# Apex4ROBOTS_1_0.net
KiCad netlist of a schematic drawn in EAGLE
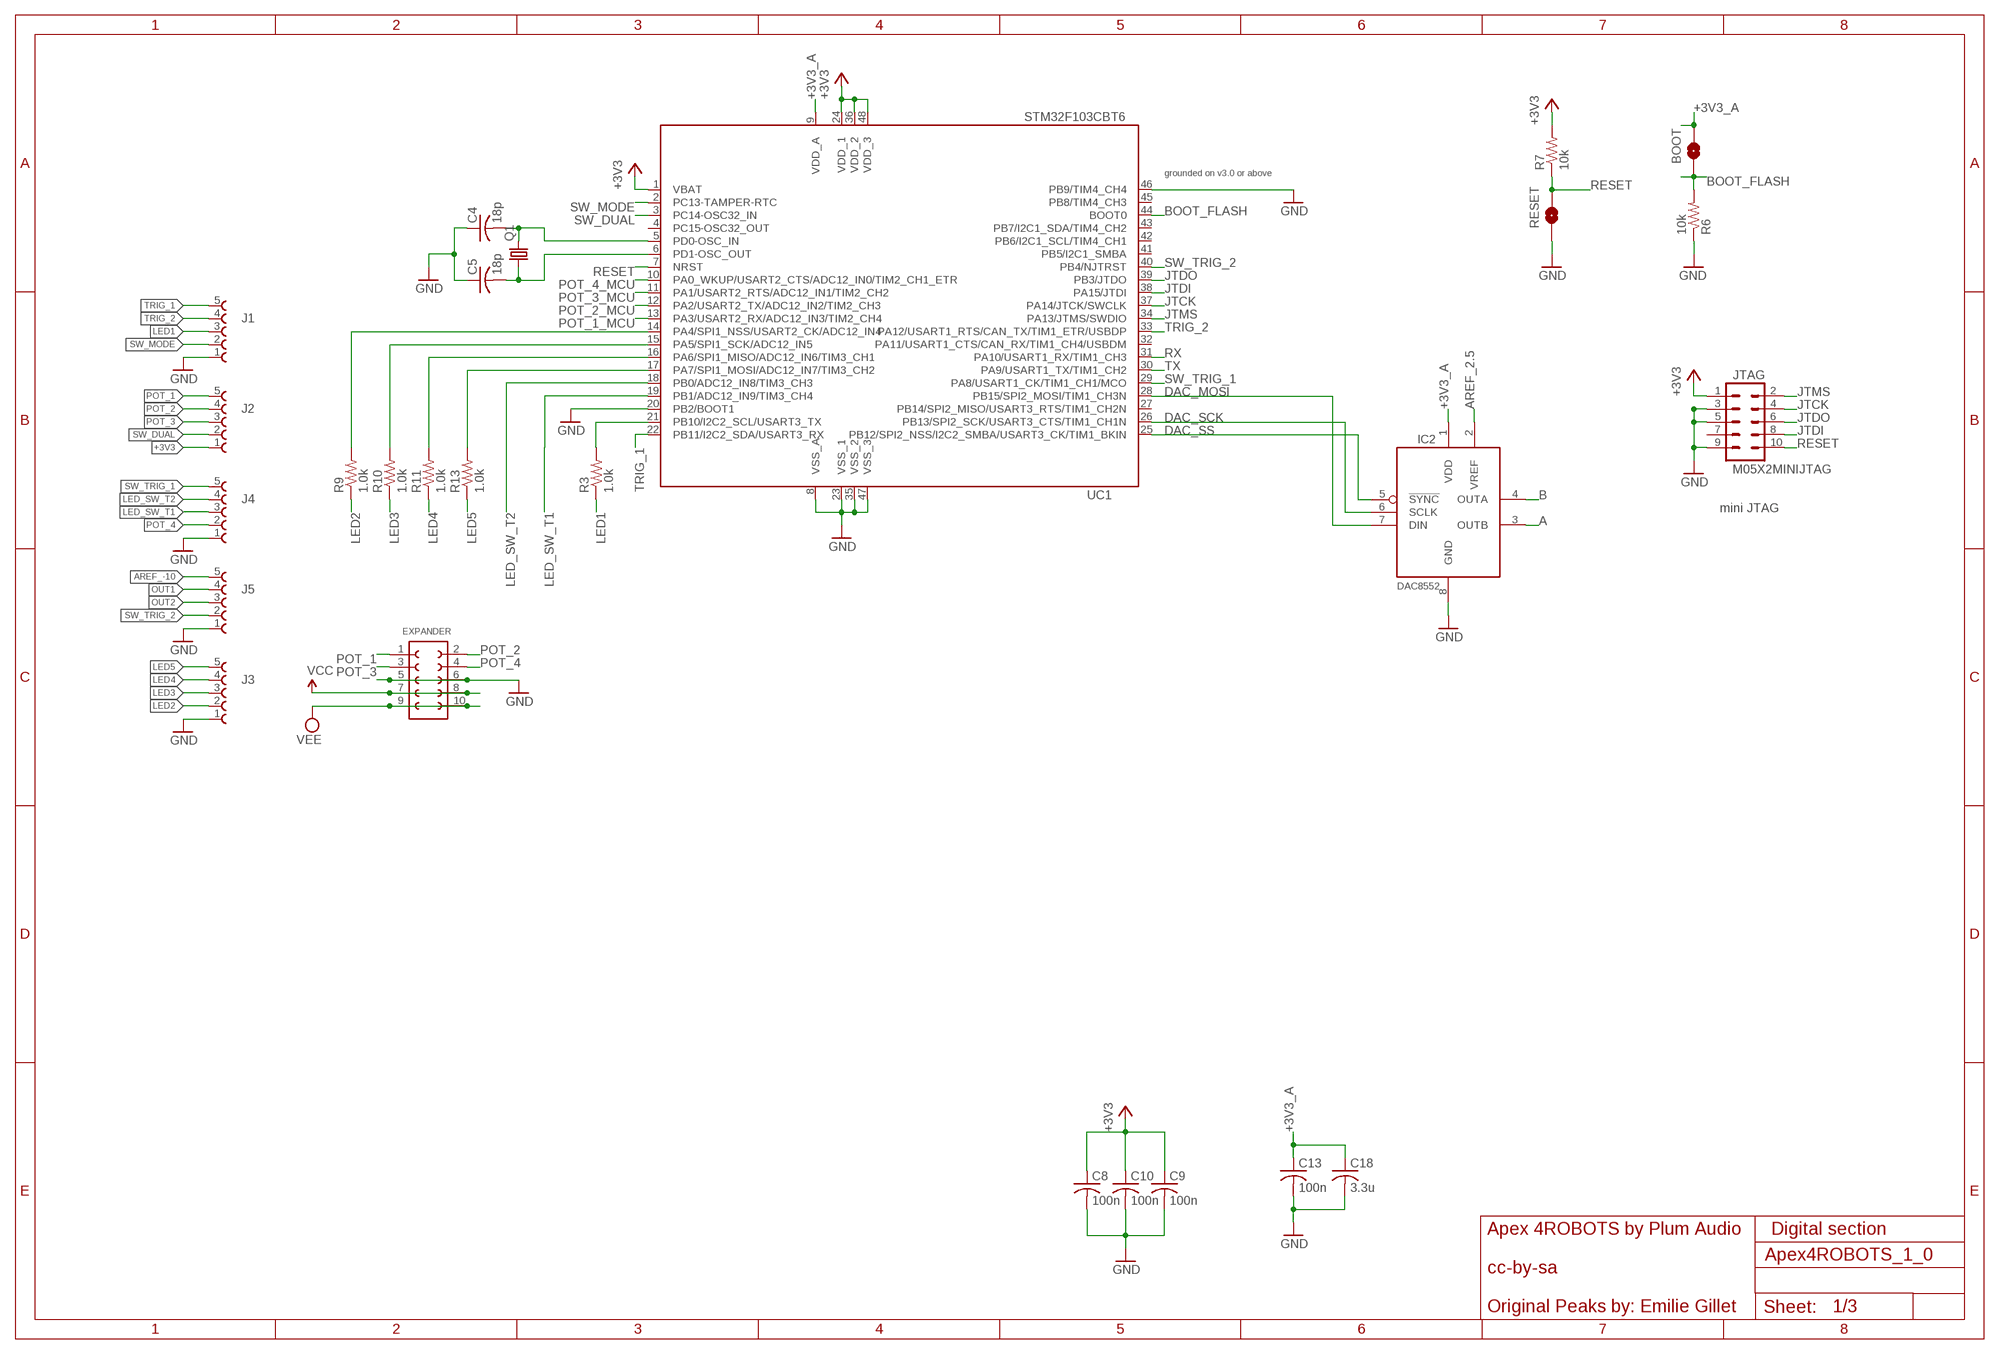
[diagram p0: schematic, sheet 1]
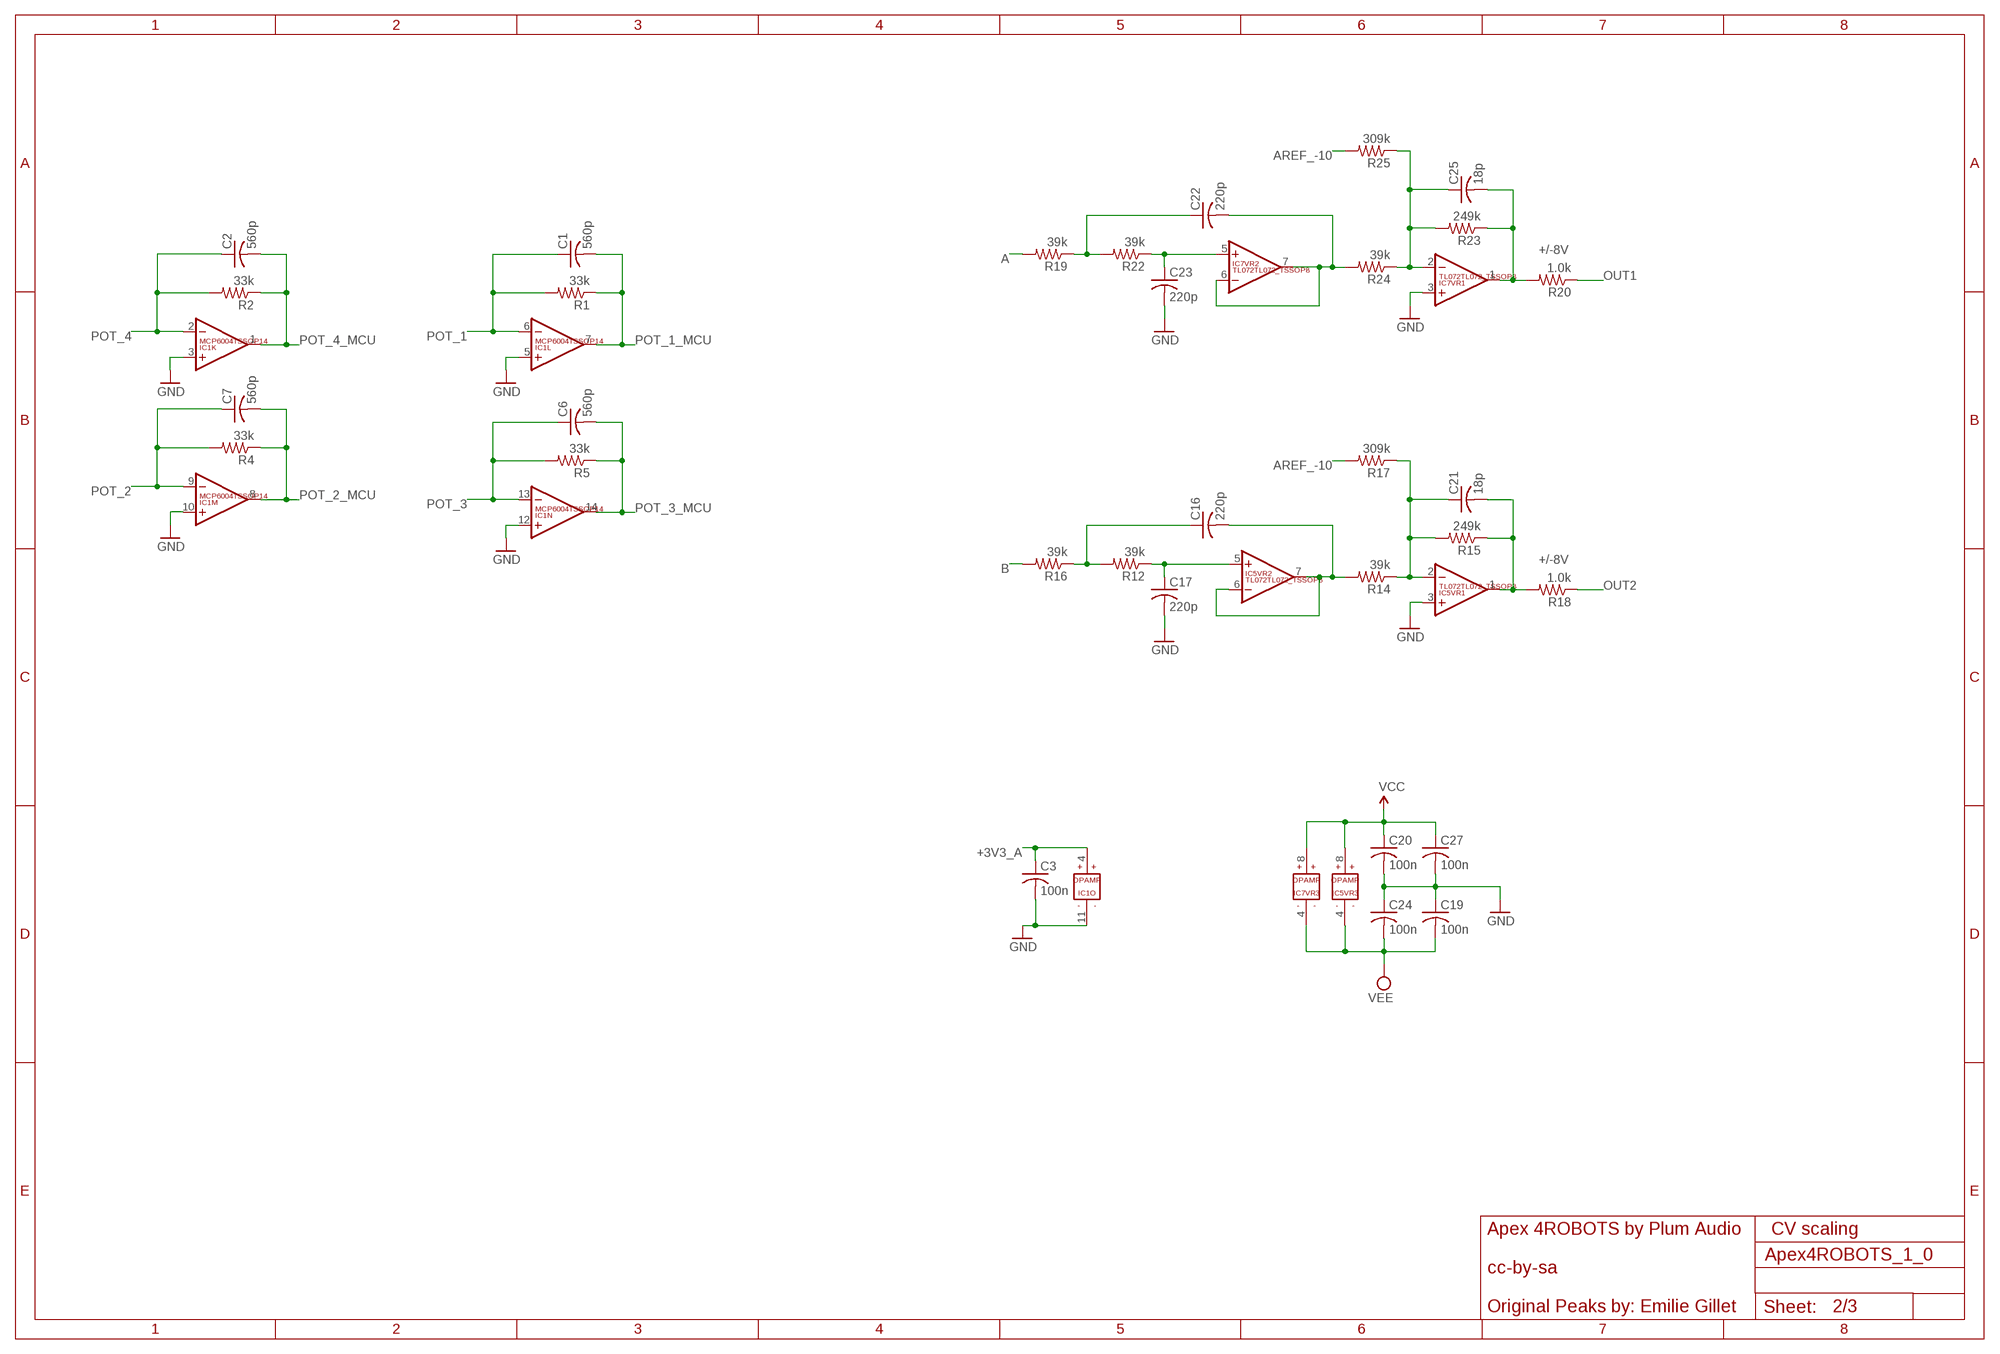
[diagram p1: schematic, sheet 2]
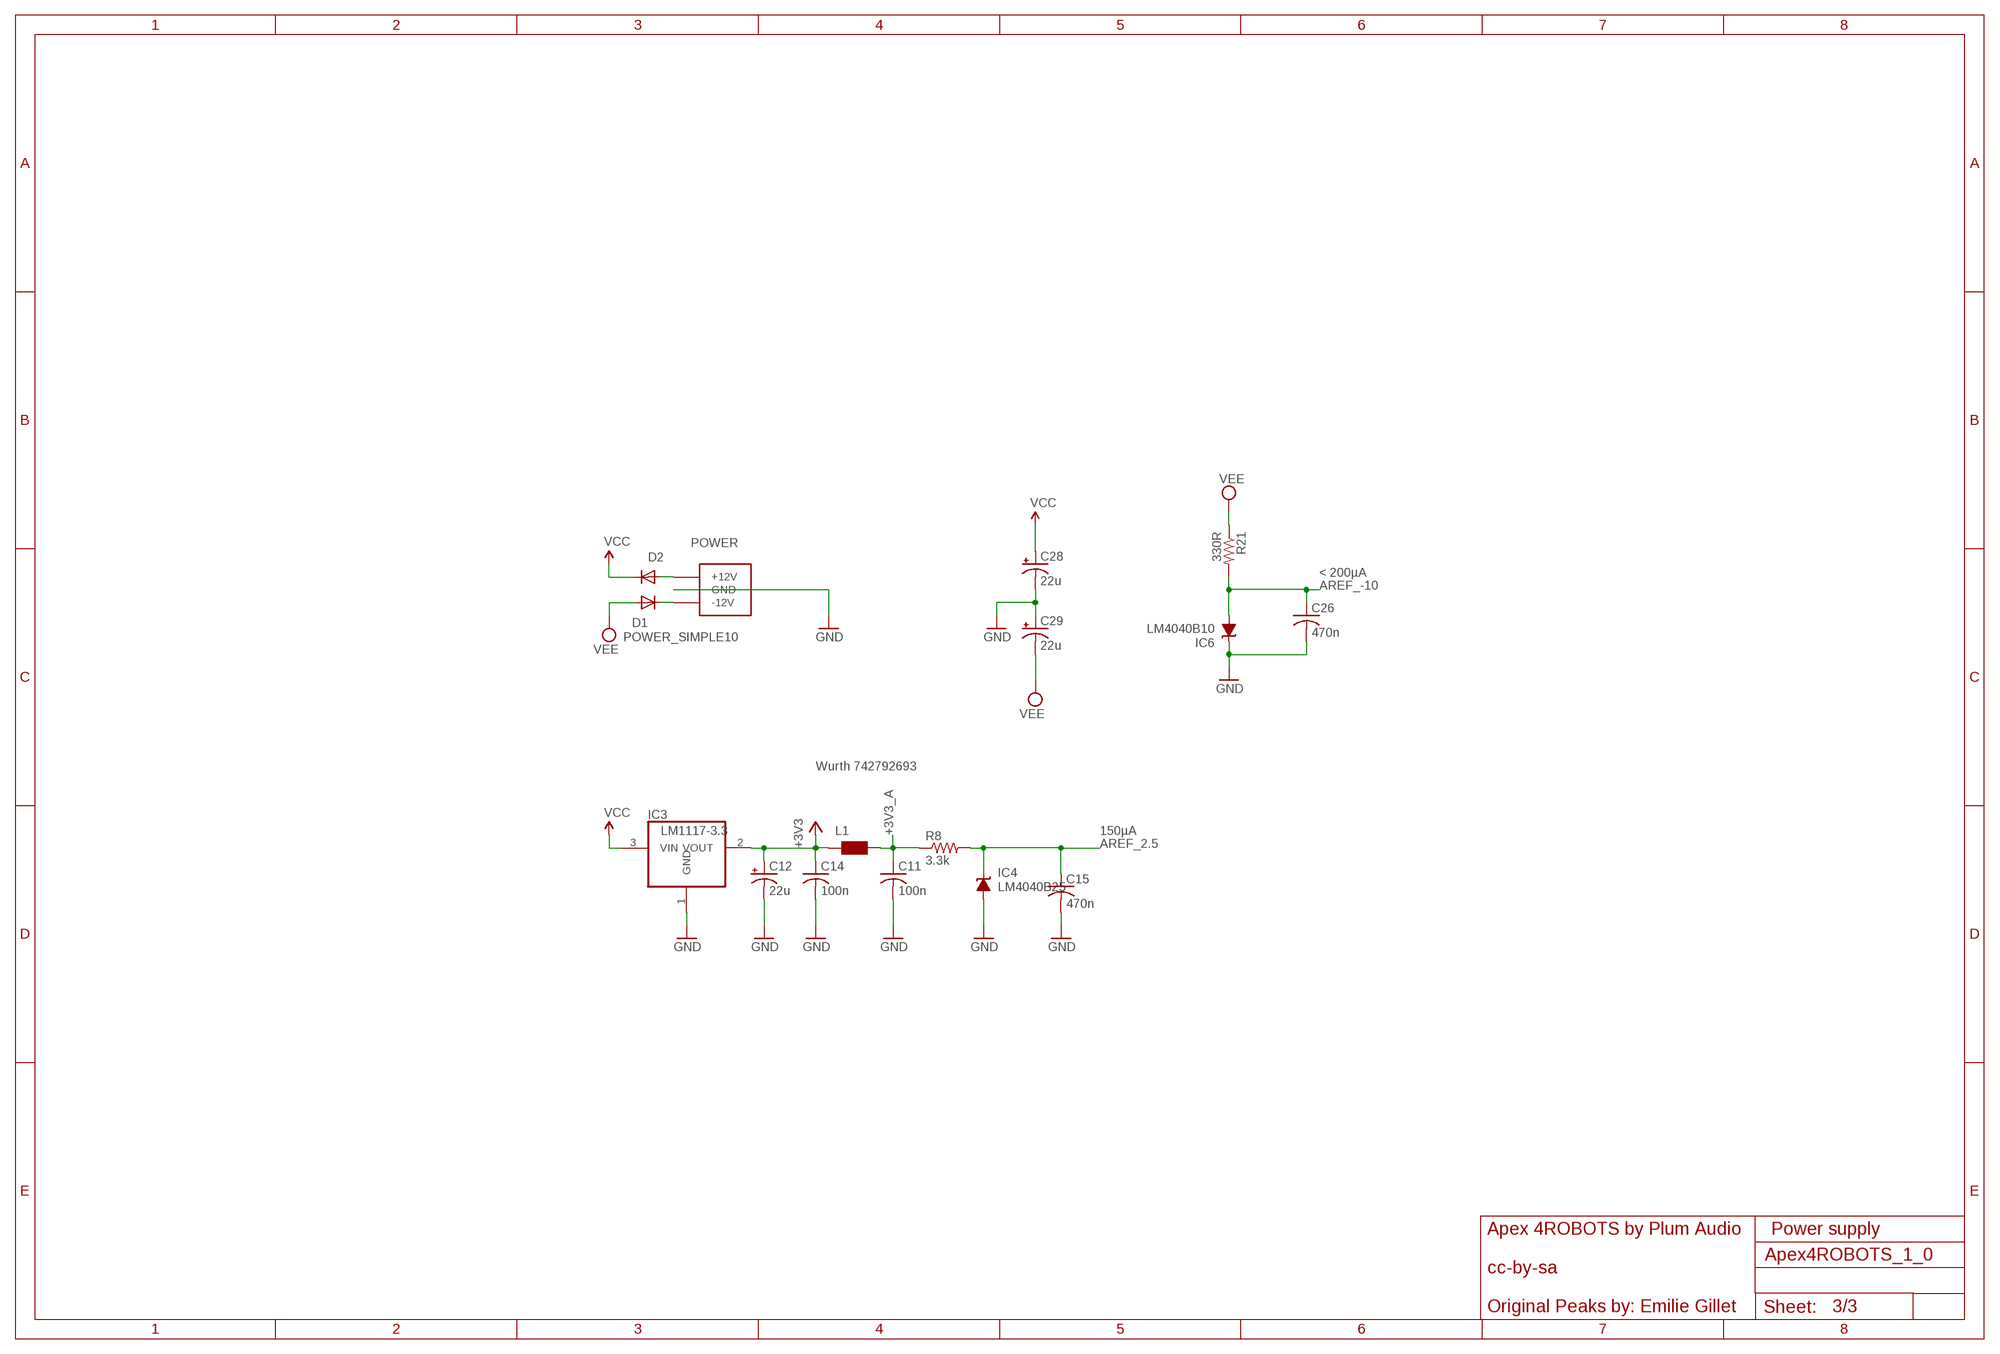
[diagram p2: schematic, sheet 3]

(export (version "E")
  (design (tool "Eeschema 10.0.6"))
  (components
    (comp (ref "C1")
      (value "560p")
      (footprint "eagle-import:C0603")
      (libsource (lib "eagle-import") (part "C-USC0603"))
    )
    (comp (ref "C2")
      (value "560p")
      (footprint "eagle-import:C0603")
      (libsource (lib "eagle-import") (part "C-USC0603"))
    )
    (comp (ref "C3")
      (value "100n")
      (footprint "eagle-import:C0603")
      (libsource (lib "eagle-import") (part "C-USC0603"))
    )
    (comp (ref "C6")
      (value "560p")
      (footprint "eagle-import:C0603")
      (libsource (lib "eagle-import") (part "C-USC0603"))
    )
    (comp (ref "C7")
      (value "560p")
      (footprint "eagle-import:C0603")
      (libsource (lib "eagle-import") (part "C-USC0603"))
    )
    (comp (ref "C16")
      (value "220p")
      (footprint "eagle-import:C0603")
      (libsource (lib "eagle-import") (part "C-USC0603"))
    )
    (comp (ref "C17")
      (value "220p")
      (footprint "eagle-import:C0603")
      (libsource (lib "eagle-import") (part "C-USC0603"))
    )
    (comp (ref "C19")
      (value "100n")
      (footprint "eagle-import:C0603")
      (libsource (lib "eagle-import") (part "C-USC0603"))
    )
    (comp (ref "C20")
      (value "100n")
      (footprint "eagle-import:C0603")
      (libsource (lib "eagle-import") (part "C-USC0603"))
    )
    (comp (ref "C21")
      (value "18p")
      (footprint "eagle-import:C0603")
      (libsource (lib "eagle-import") (part "C-USC0603"))
    )
    (comp (ref "C22")
      (value "220p")
      (footprint "eagle-import:C0603")
      (libsource (lib "eagle-import") (part "C-USC0603"))
    )
    (comp (ref "C23")
      (value "220p")
      (footprint "eagle-import:C0603")
      (libsource (lib "eagle-import") (part "C-USC0603"))
    )
    (comp (ref "C24")
      (value "100n")
      (footprint "eagle-import:C0603")
      (libsource (lib "eagle-import") (part "C-USC0603"))
    )
    (comp (ref "C25")
      (value "18p")
      (footprint "eagle-import:C0603")
      (libsource (lib "eagle-import") (part "C-USC0603"))
    )
    (comp (ref "C27")
      (value "100n")
      (footprint "eagle-import:C0603")
      (libsource (lib "eagle-import") (part "C-USC0603"))
    )
    (comp (ref "IC1")
      (value "MCP6004TSSOP14")
      (footprint "eagle-import:TSSOP14")
      (libsource (lib "eagle-import") (part "MCP6004TSSOP14"))
    )
    (comp (ref "IC5")
      (value "TL072TL072_TSSOP8")
      (footprint "eagle-import:TL072_TSSOP8")
      (libsource (lib "eagle-import") (part "TL072TL072_TSSOP8"))
    )
    (comp (ref "IC7")
      (value "TL072TL072_TSSOP8")
      (footprint "eagle-import:TL072_TSSOP8")
      (libsource (lib "eagle-import") (part "TL072TL072_TSSOP8"))
    )
    (comp (ref "R1")
      (value "33k")
      (footprint "eagle-import:R0603")
      (libsource (lib "eagle-import") (part "R-US_R0603"))
    )
    (comp (ref "R2")
      (value "33k")
      (footprint "eagle-import:R0603")
      (libsource (lib "eagle-import") (part "R-US_R0603"))
    )
    (comp (ref "R4")
      (value "33k")
      (footprint "eagle-import:R0603")
      (libsource (lib "eagle-import") (part "R-US_R0603"))
    )
    (comp (ref "R5")
      (value "33k")
      (footprint "eagle-import:R0603")
      (libsource (lib "eagle-import") (part "R-US_R0603"))
    )
    (comp (ref "R12")
      (value "39k")
      (footprint "eagle-import:R0603")
      (libsource (lib "eagle-import") (part "R-US_R0603"))
    )
    (comp (ref "R14")
      (value "39k")
      (footprint "eagle-import:R0603")
      (libsource (lib "eagle-import") (part "R-US_R0603"))
    )
    (comp (ref "R15")
      (value "249k")
      (footprint "eagle-import:R0603")
      (libsource (lib "eagle-import") (part "R-US_R0603"))
    )
    (comp (ref "R16")
      (value "39k")
      (footprint "eagle-import:R0603")
      (libsource (lib "eagle-import") (part "R-US_R0603"))
    )
    (comp (ref "R17")
      (value "309k")
      (footprint "eagle-import:R0603")
      (libsource (lib "eagle-import") (part "R-US_R0603"))
    )
    (comp (ref "R18")
      (value "1.0k")
      (footprint "eagle-import:R0603")
      (libsource (lib "eagle-import") (part "R-US_R0603"))
    )
    (comp (ref "R19")
      (value "39k")
      (footprint "eagle-import:R0603")
      (libsource (lib "eagle-import") (part "R-US_R0603"))
    )
    (comp (ref "R20")
      (value "1.0k")
      (footprint "eagle-import:R0603")
      (libsource (lib "eagle-import") (part "R-US_R0603"))
    )
    (comp (ref "R22")
      (value "39k")
      (footprint "eagle-import:R0603")
      (libsource (lib "eagle-import") (part "R-US_R0603"))
    )
    (comp (ref "R23")
      (value "249k")
      (footprint "eagle-import:R0603")
      (libsource (lib "eagle-import") (part "R-US_R0603"))
    )
    (comp (ref "R24")
      (value "39k")
      (footprint "eagle-import:R0603")
      (libsource (lib "eagle-import") (part "R-US_R0603"))
    )
    (comp (ref "R25")
      (value "309k")
      (footprint "eagle-import:R0603")
      (libsource (lib "eagle-import") (part "R-US_R0603"))
    )
    (comp (ref "BOOT")
      (value "BOOT")
      (footprint "eagle-import:SMT-JUMPER_2_NO_SILK")
      (libsource (lib "eagle-import") (part "JUMPER-SMT_2_NO_SILK"))
    )
    (comp (ref "C4")
      (value "18p")
      (footprint "eagle-import:C0603")
      (libsource (lib "eagle-import") (part "C-USC0603"))
    )
    (comp (ref "C5")
      (value "18p")
      (footprint "eagle-import:C0603")
      (libsource (lib "eagle-import") (part "C-USC0603"))
    )
    (comp (ref "C8")
      (value "100n")
      (footprint "eagle-import:C0603")
      (libsource (lib "eagle-import") (part "C-USC0603"))
    )
    (comp (ref "C9")
      (value "100n")
      (footprint "eagle-import:C0603")
      (libsource (lib "eagle-import") (part "C-USC0603"))
    )
    (comp (ref "C10")
      (value "100n")
      (footprint "eagle-import:C0603")
      (libsource (lib "eagle-import") (part "C-USC0603"))
    )
    (comp (ref "C13")
      (value "100n")
      (footprint "eagle-import:C0603")
      (libsource (lib "eagle-import") (part "C-USC0603"))
    )
    (comp (ref "C18")
      (value "3.3u")
      (footprint "eagle-import:C0603")
      (libsource (lib "eagle-import") (part "C-USC0603"))
    )
    (comp (ref "EXPANDER")
      (value "61301021121")
      (footprint "eagle-import:61301021121")
      (libsource (lib "eagle-import") (part "61301021121"))
    )
    (comp (ref "IC2")
      (value "DAC8552")
      (footprint "eagle-import:MSOP-8")
      (libsource (lib "eagle-import") (part "DAC8552"))
    )
    (comp (ref "J1")
      (value "61300511121")
      (footprint "eagle-import:61300511121")
      (libsource (lib "eagle-import") (part "61300511121"))
    )
    (comp (ref "J2")
      (value "61300511121")
      (footprint "eagle-import:61300511121")
      (libsource (lib "eagle-import") (part "61300511121"))
    )
    (comp (ref "J3")
      (value "61300511121")
      (footprint "eagle-import:61300511121")
      (libsource (lib "eagle-import") (part "61300511121"))
    )
    (comp (ref "J4")
      (value "61300511121")
      (footprint "eagle-import:61300511121")
      (libsource (lib "eagle-import") (part "61300511121"))
    )
    (comp (ref "J5")
      (value "61300511121")
      (footprint "eagle-import:61300511121")
      (libsource (lib "eagle-import") (part "61300511121"))
    )
    (comp (ref "JTAG")
      (value "M05X2MINIJTAG")
      (footprint "eagle-import:2X5-1.27")
      (libsource (lib "eagle-import") (part "M05X2MINIJTAG"))
    )
    (comp (ref "Q1")
      (value "CRYSTAL7A")
      (footprint "eagle-import:XTAL500X320X120")
      (libsource (lib "eagle-import") (part "CRYSTAL7A"))
    )
    (comp (ref "R3")
      (value "1.0k")
      (footprint "eagle-import:R0603")
      (libsource (lib "eagle-import") (part "R-US_R0603"))
    )
    (comp (ref "R6")
      (value "10k")
      (footprint "eagle-import:R0603")
      (libsource (lib "eagle-import") (part "R-US_R0603"))
    )
    (comp (ref "R7")
      (value "10k")
      (footprint "eagle-import:R0603")
      (libsource (lib "eagle-import") (part "R-US_R0603"))
    )
    (comp (ref "R9")
      (value "1.0k")
      (footprint "eagle-import:R0603")
      (libsource (lib "eagle-import") (part "R-US_R0603"))
    )
    (comp (ref "R10")
      (value "1.0k")
      (footprint "eagle-import:R0603")
      (libsource (lib "eagle-import") (part "R-US_R0603"))
    )
    (comp (ref "R11")
      (value "1.0k")
      (footprint "eagle-import:R0603")
      (libsource (lib "eagle-import") (part "R-US_R0603"))
    )
    (comp (ref "R13")
      (value "1.0k")
      (footprint "eagle-import:R0603")
      (libsource (lib "eagle-import") (part "R-US_R0603"))
    )
    (comp (ref "RESET")
      (value "RESET")
      (footprint "eagle-import:SMT-JUMPER_2_NO_SILK")
      (libsource (lib "eagle-import") (part "JUMPER-SMT_2_NO_SILK"))
    )
    (comp (ref "UC1")
      (value "STM32F103CBT6")
      (footprint "eagle-import:LQFP48")
      (libsource (lib "eagle-import") (part "STM32F103CB"))
    )
    (comp (ref "C11")
      (value "100n")
      (footprint "eagle-import:C0603")
      (libsource (lib "eagle-import") (part "C-USC0603"))
    )
    (comp (ref "C12")
      (value "22u")
      (footprint "eagle-import:PANASONIC_C")
      (libsource (lib "eagle-import") (part "CPOL-USC"))
    )
    (comp (ref "C14")
      (value "100n")
      (footprint "eagle-import:C0603")
      (libsource (lib "eagle-import") (part "C-USC0603"))
    )
    (comp (ref "C15")
      (value "470n")
      (footprint "eagle-import:C0603")
      (libsource (lib "eagle-import") (part "C-USC0603"))
    )
    (comp (ref "C26")
      (value "470n")
      (footprint "eagle-import:C0603")
      (libsource (lib "eagle-import") (part "C-USC0603"))
    )
    (comp (ref "C28")
      (value "22u")
      (footprint "eagle-import:PANASONIC_C")
      (libsource (lib "eagle-import") (part "CPOL-USC"))
    )
    (comp (ref "C29")
      (value "22u")
      (footprint "eagle-import:PANASONIC_C")
      (libsource (lib "eagle-import") (part "CPOL-USC"))
    )
    (comp (ref "D1")
      (value "1N5819HW")
      (footprint "eagle-import:SOD123")
      (libsource (lib "eagle-import") (part "DIODE-SOD123"))
    )
    (comp (ref "D2")
      (value "1N5819HW")
      (footprint "eagle-import:SOD123")
      (libsource (lib "eagle-import") (part "DIODE-SOD123"))
    )
    (comp (ref "IC3")
      (value "LM1117-3.3")
      (footprint "eagle-import:SOT223")
      (libsource (lib "eagle-import") (part "REG1117"))
    )
    (comp (ref "IC4")
      (value "LM4040B25")
      (footprint "eagle-import:DBZ_R-PDSO-G3")
      (libsource (lib "eagle-import") (part "LM4041DBZB12"))
    )
    (comp (ref "IC6")
      (value "LM4040B10")
      (footprint "eagle-import:DBZ_R-PDSO-G3")
      (libsource (lib "eagle-import") (part "LM4041DBZB12"))
    )
    (comp (ref "L1")
      (value "WE-CBF_0603")
      (footprint "eagle-import:0603")
      (libsource (lib "eagle-import") (part "WE-CBF_0603"))
    )
    (comp (ref "POWER")
      (value "POWER_SIMPLE10")
      (footprint "eagle-import:POWER_10")
      (libsource (lib "eagle-import") (part "POWER_SIMPLE10"))
    )
    (comp (ref "R8")
      (value "3.3k")
      (footprint "eagle-import:R0603")
      (libsource (lib "eagle-import") (part "R-US_R0603"))
    )
    (comp (ref "R21")
      (value "330R")
      (footprint "eagle-import:R0603")
      (libsource (lib "eagle-import") (part "R-US_R0603"))
    )
  )
  (nets
    (net (code "1") (name "+3V3") (class "Default")
      (node (ref "C10") (pin "1") (pinfunction "1_1") (pintype "passive"))
      (node (ref "C12") (pin "+") (pinfunction "+_+") (pintype "passive"))
      (node (ref "C14") (pin "1") (pinfunction "1_1") (pintype "passive"))
      (node (ref "C8") (pin "1") (pinfunction "1_1") (pintype "passive"))
      (node (ref "C9") (pin "1") (pinfunction "1_1") (pintype "passive"))
      (node (ref "IC3") (pin "2") (pinfunction "VOUT_2") (pintype "output"))
      (node (ref "J2") (pin "1") (pinfunction "5_1") (pintype "passive"))
      (node (ref "JTAG") (pin "1") (pinfunction "1_1") (pintype "passive"))
      (node (ref "L1") (pin "1") (pinfunction "1_1") (pintype "passive"))
      (node (ref "R7") (pin "2") (pinfunction "2_2") (pintype "passive"))
      (node (ref "UC1") (pin "1") (pinfunction "VBAT_1") (pintype "power_in"))
      (node (ref "UC1") (pin "24") (pinfunction "VDD_1_24") (pintype "power_in"))
      (node (ref "UC1") (pin "36") (pinfunction "VDD_2_36") (pintype "power_in"))
      (node (ref "UC1") (pin "48") (pinfunction "VDD_3_48") (pintype "power_in"))
    )
    (net (code "2") (name "+3V3_A") (class "Default")
      (node (ref "BOOT") (pin "2") (pinfunction "2_2") (pintype "passive"))
      (node (ref "C11") (pin "1") (pinfunction "1_1") (pintype "passive"))
      (node (ref "C13") (pin "1") (pinfunction "1_1") (pintype "passive"))
      (node (ref "C18") (pin "1") (pinfunction "1_1") (pintype "passive"))
      (node (ref "C3") (pin "1") (pinfunction "1_1") (pintype "passive"))
      (node (ref "IC1") (pin "4") (pinfunction "V+_4") (pintype "power_in"))
      (node (ref "IC2") (pin "1") (pinfunction "VDD_1") (pintype "power_in"))
      (node (ref "L1") (pin "2") (pinfunction "2_2") (pintype "passive"))
      (node (ref "R8") (pin "1") (pinfunction "1_1") (pintype "passive"))
      (node (ref "UC1") (pin "9") (pinfunction "VDD_A_9") (pintype "power_in"))
    )
    (net (code "3") (name "A") (class "Default")
      (node (ref "IC2") (pin "3") (pinfunction "OUTB_3") (pintype "input"))
      (node (ref "R19") (pin "2") (pinfunction "2_2") (pintype "passive"))
    )
    (net (code "4") (name "AREF_-10") (class "Default")
      (node (ref "C26") (pin "1") (pinfunction "1_1") (pintype "passive"))
      (node (ref "IC6") (pin "2") (pinfunction "A_2") (pintype "passive"))
      (node (ref "J5") (pin "5") (pinfunction "1_5") (pintype "passive"))
      (node (ref "R17") (pin "2") (pinfunction "2_2") (pintype "passive"))
      (node (ref "R21") (pin "2") (pinfunction "2_2") (pintype "passive"))
      (node (ref "R25") (pin "2") (pinfunction "2_2") (pintype "passive"))
    )
    (net (code "5") (name "AREF_2.5") (class "Default")
      (node (ref "C15") (pin "1") (pinfunction "1_1") (pintype "passive"))
      (node (ref "IC2") (pin "2") (pinfunction "VREF_2") (pintype "power_in"))
      (node (ref "IC4") (pin "1") (pinfunction "C_1") (pintype "passive"))
      (node (ref "R8") (pin "2") (pinfunction "2_2") (pintype "passive"))
    )
    (net (code "6") (name "B") (class "Default")
      (node (ref "IC2") (pin "4") (pinfunction "OUTA_4") (pintype "output"))
      (node (ref "R16") (pin "2") (pinfunction "2_2") (pintype "passive"))
    )
    (net (code "7") (name "BOOT_FLASH") (class "Default")
      (node (ref "BOOT") (pin "1") (pinfunction "1_1") (pintype "passive"))
      (node (ref "R6") (pin "2") (pinfunction "2_2") (pintype "passive"))
      (node (ref "UC1") (pin "44") (pinfunction "BOOT0_44") (pintype "input"))
    )
    (net (code "8") (name "DAC_MOSI") (class "Default")
      (node (ref "IC2") (pin "7") (pinfunction "DIN_7") (pintype "bidirectional"))
      (node (ref "UC1") (pin "28") (pinfunction "PB15/SPI2_MOSI/TIM1_CH3N_28") (pintype "input"))
    )
    (net (code "9") (name "DAC_SCK") (class "Default")
      (node (ref "IC2") (pin "6") (pinfunction "SCLK_6") (pintype "bidirectional"))
      (node (ref "UC1") (pin "26") (pinfunction "PB13/SPI2_SCK/USART3_CTS/TIM1_CH1N_26") (pintype "input"))
    )
    (net (code "10") (name "DAC_SS") (class "Default")
      (node (ref "IC2") (pin "5") (pinfunction "~{SYNC}_5") (pintype "bidirectional"))
      (node (ref "UC1") (pin "25") (pinfunction "PB12/SPI2_NSS/I2C2_SMBA/USART3_CK/TIM1_BKIN_25") (pintype "input"))
    )
    (net (code "11") (name "GND") (class "Default")
      (node (ref "C10") (pin "2") (pinfunction "2_2") (pintype "passive"))
      (node (ref "C11") (pin "2") (pinfunction "2_2") (pintype "passive"))
      (node (ref "C12") (pin "-") (pinfunction "-_-") (pintype "passive"))
      (node (ref "C13") (pin "2") (pinfunction "2_2") (pintype "passive"))
      (node (ref "C14") (pin "2") (pinfunction "2_2") (pintype "passive"))
      (node (ref "C15") (pin "2") (pinfunction "2_2") (pintype "passive"))
      (node (ref "C17") (pin "2") (pinfunction "2_2") (pintype "passive"))
      (node (ref "C18") (pin "2") (pinfunction "2_2") (pintype "passive"))
      (node (ref "C19") (pin "1") (pinfunction "1_1") (pintype "passive"))
      (node (ref "C20") (pin "2") (pinfunction "2_2") (pintype "passive"))
      (node (ref "C23") (pin "2") (pinfunction "2_2") (pintype "passive"))
      (node (ref "C24") (pin "1") (pinfunction "1_1") (pintype "passive"))
      (node (ref "C26") (pin "2") (pinfunction "2_2") (pintype "passive"))
      (node (ref "C27") (pin "2") (pinfunction "2_2") (pintype "passive"))
      (node (ref "C28") (pin "-") (pinfunction "-_-") (pintype "passive"))
      (node (ref "C29") (pin "+") (pinfunction "+_+") (pintype "passive"))
      (node (ref "C3") (pin "2") (pinfunction "2_2") (pintype "passive"))
      (node (ref "C4") (pin "1") (pinfunction "1_1") (pintype "passive"))
      (node (ref "C5") (pin "1") (pinfunction "1_1") (pintype "passive"))
      (node (ref "C8") (pin "2") (pinfunction "2_2") (pintype "passive"))
      (node (ref "C9") (pin "2") (pinfunction "2_2") (pintype "passive"))
      (node (ref "EXPANDER") (pin "5") (pinfunction "3_5") (pintype "passive"))
      (node (ref "EXPANDER") (pin "6") (pinfunction "8_6") (pintype "passive"))
      (node (ref "IC1") (pin "10") (pinfunction "+IN_10") (pintype "input"))
      (node (ref "IC1") (pin "11") (pinfunction "V-_11") (pintype "power_in"))
      (node (ref "IC1") (pin "12") (pinfunction "+IN_12") (pintype "input"))
      (node (ref "IC1") (pin "3") (pinfunction "+IN_3") (pintype "input"))
      (node (ref "IC1") (pin "5") (pinfunction "+IN_5") (pintype "input"))
      (node (ref "IC2") (pin "8") (pinfunction "GND_8") (pintype "power_in"))
      (node (ref "IC3") (pin "1") (pinfunction "GND_1") (pintype "power_in"))
      (node (ref "IC4") (pin "2") (pinfunction "A_2") (pintype "passive"))
      (node (ref "IC5") (pin "3") (pinfunction "+IN_3") (pintype "input"))
      (node (ref "IC6") (pin "1") (pinfunction "C_1") (pintype "passive"))
      (node (ref "IC7") (pin "3") (pinfunction "+IN_3") (pintype "input"))
      (node (ref "J1") (pin "1") (pinfunction "5_1") (pintype "passive"))
      (node (ref "J3") (pin "1") (pinfunction "5_1") (pintype "passive"))
      (node (ref "J4") (pin "1") (pinfunction "5_1") (pintype "passive"))
      (node (ref "J5") (pin "1") (pinfunction "5_1") (pintype "passive"))
      (node (ref "JTAG") (pin "3") (pinfunction "3_3") (pintype "passive"))
      (node (ref "JTAG") (pin "5") (pinfunction "5_5") (pintype "passive"))
      (node (ref "JTAG") (pin "9") (pinfunction "9_9") (pintype "passive"))
      (node (ref "POWER") (pin "3") (pinfunction "GND_3") (pintype "bidirectional"))
      (node (ref "POWER") (pin "4") (pinfunction "GND_4") (pintype "bidirectional"))
      (node (ref "POWER") (pin "5") (pinfunction "GND_5") (pintype "bidirectional"))
      (node (ref "POWER") (pin "6") (pinfunction "GND_6") (pintype "bidirectional"))
      (node (ref "POWER") (pin "7") (pinfunction "GND_7") (pintype "bidirectional"))
      (node (ref "POWER") (pin "8") (pinfunction "GND_8") (pintype "bidirectional"))
      (node (ref "R6") (pin "1") (pinfunction "1_1") (pintype "passive"))
      (node (ref "RESET") (pin "1") (pinfunction "1_1") (pintype "passive"))
      (node (ref "UC1") (pin "20") (pinfunction "PB2/BOOT1_20") (pintype "bidirectional"))
      (node (ref "UC1") (pin "23") (pinfunction "VSS_1_23") (pintype "power_in"))
      (node (ref "UC1") (pin "35") (pinfunction "VSS_2_35") (pintype "power_in"))
      (node (ref "UC1") (pin "46") (pinfunction "PB9/TIM4_CH4_46") (pintype "input"))
      (node (ref "UC1") (pin "47") (pinfunction "VSS_3_47") (pintype "power_in"))
      (node (ref "UC1") (pin "8") (pinfunction "VSS_A_8") (pintype "power_in"))
    )
    (net (code "12") (name "JTCK") (class "Default")
      (node (ref "JTAG") (pin "4") (pinfunction "4_4") (pintype "passive"))
      (node (ref "UC1") (pin "37") (pinfunction "PA14/JTCK/SWCLK_37") (pintype "bidirectional"))
    )
    (net (code "13") (name "JTDI") (class "Default")
      (node (ref "JTAG") (pin "8") (pinfunction "8_8") (pintype "passive"))
      (node (ref "UC1") (pin "38") (pinfunction "PA15/JTDI_38") (pintype "bidirectional"))
    )
    (net (code "14") (name "JTDO") (class "Default")
      (node (ref "JTAG") (pin "6") (pinfunction "6_6") (pintype "passive"))
      (node (ref "UC1") (pin "39") (pinfunction "PB3/JTDO_39") (pintype "bidirectional"))
    )
    (net (code "15") (name "JTMS") (class "Default")
      (node (ref "JTAG") (pin "2") (pinfunction "2_2") (pintype "passive"))
      (node (ref "UC1") (pin "34") (pinfunction "PA13/JTMS/SWDIO_34") (pintype "bidirectional"))
    )
    (net (code "16") (name "LED1") (class "Default")
      (node (ref "J1") (pin "3") (pinfunction "3_3") (pintype "passive"))
      (node (ref "R3") (pin "1") (pinfunction "1_1") (pintype "passive"))
    )
    (net (code "17") (name "LED2") (class "Default")
      (node (ref "J3") (pin "2") (pinfunction "4_2") (pintype "passive"))
      (node (ref "R9") (pin "1") (pinfunction "1_1") (pintype "passive"))
    )
    (net (code "18") (name "LED3") (class "Default")
      (node (ref "J3") (pin "3") (pinfunction "3_3") (pintype "passive"))
      (node (ref "R10") (pin "1") (pinfunction "1_1") (pintype "passive"))
    )
    (net (code "19") (name "LED4") (class "Default")
      (node (ref "J3") (pin "4") (pinfunction "2_4") (pintype "passive"))
      (node (ref "R11") (pin "1") (pinfunction "1_1") (pintype "passive"))
    )
    (net (code "20") (name "LED5") (class "Default")
      (node (ref "J3") (pin "5") (pinfunction "1_5") (pintype "passive"))
      (node (ref "R13") (pin "1") (pinfunction "1_1") (pintype "passive"))
    )
    (net (code "21") (name "LED_SW_T1") (class "Default")
      (node (ref "J4") (pin "3") (pinfunction "3_3") (pintype "passive"))
      (node (ref "UC1") (pin "19") (pinfunction "PB1/ADC12_IN9/TIM3_CH4_19") (pintype "bidirectional"))
    )
    (net (code "22") (name "LED_SW_T2") (class "Default")
      (node (ref "J4") (pin "4") (pinfunction "2_4") (pintype "passive"))
      (node (ref "UC1") (pin "18") (pinfunction "PB0/ADC12_IN8/TIM3_CH3_18") (pintype "bidirectional"))
    )
    (net (code "23") (name "Net-(C16-Pad1)") (class "Default")
      (node (ref "C16") (pin "1") (pinfunction "1_1") (pintype "passive"))
      (node (ref "R12") (pin "2") (pinfunction "2_2") (pintype "passive"))
      (node (ref "R16") (pin "1") (pinfunction "1_1") (pintype "passive"))
    )
    (net (code "24") (name "Net-(C22-Pad1)") (class "Default")
      (node (ref "C22") (pin "1") (pinfunction "1_1") (pintype "passive"))
      (node (ref "R19") (pin "1") (pinfunction "1_1") (pintype "passive"))
      (node (ref "R22") (pin "2") (pinfunction "2_2") (pintype "passive"))
    )
    (net (code "25") (name "Net-(D1-PadC)") (class "Default")
      (node (ref "D1") (pin "C") (pinfunction "C_C") (pintype "passive"))
      (node (ref "POWER") (pin "1") (pinfunction "-12V_1") (pintype "bidirectional"))
      (node (ref "POWER") (pin "2") (pinfunction "-12V_2") (pintype "bidirectional"))
    )
    (net (code "26") (name "Net-(D2-PadA)") (class "Default")
      (node (ref "D2") (pin "A") (pinfunction "A_A") (pintype "passive"))
      (node (ref "POWER") (pin "10") (pinfunction "+12V_10") (pintype "bidirectional"))
      (node (ref "POWER") (pin "9") (pinfunction "+12V_9") (pintype "bidirectional"))
    )
    (net (code "27") (name "Net-(IC5A--IN)") (class "Default")
      (node (ref "C21") (pin "1") (pinfunction "1_1") (pintype "passive"))
      (node (ref "IC5") (pin "2") (pinfunction "-IN_2") (pintype "input"))
      (node (ref "R14") (pin "1") (pinfunction "1_1") (pintype "passive"))
      (node (ref "R15") (pin "2") (pinfunction "2_2") (pintype "passive"))
      (node (ref "R17") (pin "1") (pinfunction "1_1") (pintype "passive"))
    )
    (net (code "28") (name "Net-(IC5A-OUT)") (class "Default")
      (node (ref "C21") (pin "2") (pinfunction "2_2") (pintype "passive"))
      (node (ref "IC5") (pin "1") (pinfunction "OUT_1") (pintype "output"))
      (node (ref "R15") (pin "1") (pinfunction "1_1") (pintype "passive"))
      (node (ref "R18") (pin "2") (pinfunction "2_2") (pintype "passive"))
    )
    (net (code "29") (name "Net-(IC5B-+IN)") (class "Default")
      (node (ref "C17") (pin "1") (pinfunction "1_1") (pintype "passive"))
      (node (ref "IC5") (pin "5") (pinfunction "+IN_5") (pintype "input"))
      (node (ref "R12") (pin "1") (pinfunction "1_1") (pintype "passive"))
    )
    (net (code "30") (name "Net-(IC5B--IN)") (class "Default")
      (node (ref "C16") (pin "2") (pinfunction "2_2") (pintype "passive"))
      (node (ref "IC5") (pin "6") (pinfunction "-IN_6") (pintype "input"))
      (node (ref "IC5") (pin "7") (pinfunction "OUT_7") (pintype "output"))
      (node (ref "R14") (pin "2") (pinfunction "2_2") (pintype "passive"))
    )
    (net (code "31") (name "Net-(IC7A--IN)") (class "Default")
      (node (ref "C25") (pin "1") (pinfunction "1_1") (pintype "passive"))
      (node (ref "IC7") (pin "2") (pinfunction "-IN_2") (pintype "input"))
      (node (ref "R23") (pin "2") (pinfunction "2_2") (pintype "passive"))
      (node (ref "R24") (pin "1") (pinfunction "1_1") (pintype "passive"))
      (node (ref "R25") (pin "1") (pinfunction "1_1") (pintype "passive"))
    )
    (net (code "32") (name "Net-(IC7A-OUT)") (class "Default")
      (node (ref "C25") (pin "2") (pinfunction "2_2") (pintype "passive"))
      (node (ref "IC7") (pin "1") (pinfunction "OUT_1") (pintype "output"))
      (node (ref "R20") (pin "2") (pinfunction "2_2") (pintype "passive"))
      (node (ref "R23") (pin "1") (pinfunction "1_1") (pintype "passive"))
    )
    (net (code "33") (name "Net-(IC7B-+IN)") (class "Default")
      (node (ref "C23") (pin "1") (pinfunction "1_1") (pintype "passive"))
      (node (ref "IC7") (pin "5") (pinfunction "+IN_5") (pintype "input"))
      (node (ref "R22") (pin "1") (pinfunction "1_1") (pintype "passive"))
    )
    (net (code "34") (name "Net-(IC7B--IN)") (class "Default")
      (node (ref "C22") (pin "2") (pinfunction "2_2") (pintype "passive"))
      (node (ref "IC7") (pin "6") (pinfunction "-IN_6") (pintype "input"))
      (node (ref "IC7") (pin "7") (pinfunction "OUT_7") (pintype "output"))
      (node (ref "R24") (pin "2") (pinfunction "2_2") (pintype "passive"))
    )
    (net (code "35") (name "Net-(UC1-PA4{slash}SPI1_NSS{slash}USART2_CK{slash}ADC12_IN4)") (class "Default")
      (node (ref "R9") (pin "2") (pinfunction "2_2") (pintype "passive"))
      (node (ref "UC1") (pin "14") (pinfunction "PA4/SPI1_NSS/USART2_CK/ADC12_IN4_14") (pintype "bidirectional"))
    )
    (net (code "36") (name "Net-(UC1-PA5{slash}SPI1_SCK{slash}ADC12_IN5)") (class "Default")
      (node (ref "R10") (pin "2") (pinfunction "2_2") (pintype "passive"))
      (node (ref "UC1") (pin "15") (pinfunction "PA5/SPI1_SCK/ADC12_IN5_15") (pintype "bidirectional"))
    )
    (net (code "37") (name "Net-(UC1-PA6{slash}SPI1_MISO{slash}ADC12_IN6{slash}TIM3_CH1)") (class "Default")
      (node (ref "R11") (pin "2") (pinfunction "2_2") (pintype "passive"))
      (node (ref "UC1") (pin "16") (pinfunction "PA6/SPI1_MISO/ADC12_IN6/TIM3_CH1_16") (pintype "bidirectional"))
    )
    (net (code "38") (name "Net-(UC1-PA7{slash}SPI1_MOSI{slash}ADC12_IN7{slash}TIM3_CH2)") (class "Default")
      (node (ref "R13") (pin "2") (pinfunction "2_2") (pintype "passive"))
      (node (ref "UC1") (pin "17") (pinfunction "PA7/SPI1_MOSI/ADC12_IN7/TIM3_CH2_17") (pintype "bidirectional"))
    )
    (net (code "39") (name "Net-(UC1-PB10{slash}I2C2_SCL{slash}USART3_TX)") (class "Default")
      (node (ref "R3") (pin "2") (pinfunction "2_2") (pintype "passive"))
      (node (ref "UC1") (pin "21") (pinfunction "PB10/I2C2_SCL/USART3_TX_21") (pintype "input"))
    )
    (net (code "40") (name "Net-(UC1-PD0-OSC_IN)") (class "Default")
      (node (ref "C4") (pin "2") (pinfunction "2_2") (pintype "passive"))
      (node (ref "Q1") (pin "2") (pinfunction "2_2") (pintype "passive"))
      (node (ref "UC1") (pin "5") (pinfunction "PD0-OSC_IN_5") (pintype "input"))
    )
    (net (code "41") (name "Net-(UC1-PD1-OSC_OUT)") (class "Default")
      (node (ref "C5") (pin "2") (pinfunction "2_2") (pintype "passive"))
      (node (ref "Q1") (pin "1") (pinfunction "1_1") (pintype "passive"))
      (node (ref "UC1") (pin "6") (pinfunction "PD1-OSC_OUT_6") (pintype "input"))
    )
    (net (code "42") (name "OUT1") (class "Default")
      (node (ref "J5") (pin "4") (pinfunction "2_4") (pintype "passive"))
      (node (ref "R20") (pin "1") (pinfunction "1_1") (pintype "passive"))
    )
    (net (code "43") (name "OUT2") (class "Default")
      (node (ref "J5") (pin "3") (pinfunction "3_3") (pintype "passive"))
      (node (ref "R18") (pin "1") (pinfunction "1_1") (pintype "passive"))
    )
    (net (code "44") (name "POT_1") (class "Default")
      (node (ref "C1") (pin "1") (pinfunction "1_1") (pintype "passive"))
      (node (ref "EXPANDER") (pin "1") (pinfunction "1_1") (pintype "passive"))
      (node (ref "IC1") (pin "6") (pinfunction "-IN_6") (pintype "input"))
      (node (ref "J2") (pin "5") (pinfunction "1_5") (pintype "passive"))
      (node (ref "R1") (pin "2") (pinfunction "2_2") (pintype "passive"))
    )
    (net (code "45") (name "POT_1_MCU") (class "Default")
      (node (ref "C1") (pin "2") (pinfunction "2_2") (pintype "passive"))
      (node (ref "IC1") (pin "7") (pinfunction "OUT_7") (pintype "output"))
      (node (ref "R1") (pin "1") (pinfunction "1_1") (pintype "passive"))
      (node (ref "UC1") (pin "13") (pinfunction "PA3/USART2_RX/ADC12_IN3/TIM2_CH4_13") (pintype "bidirectional"))
    )
    (net (code "46") (name "POT_2") (class "Default")
      (node (ref "C7") (pin "1") (pinfunction "1_1") (pintype "passive"))
      (node (ref "EXPANDER") (pin "2") (pinfunction "10_2") (pintype "passive"))
      (node (ref "IC1") (pin "9") (pinfunction "-IN_9") (pintype "input"))
      (node (ref "J2") (pin "4") (pinfunction "2_4") (pintype "passive"))
      (node (ref "R4") (pin "2") (pinfunction "2_2") (pintype "passive"))
    )
    (net (code "47") (name "POT_2_MCU") (class "Default")
      (node (ref "C7") (pin "2") (pinfunction "2_2") (pintype "passive"))
      (node (ref "IC1") (pin "8") (pinfunction "OUT_8") (pintype "output"))
      (node (ref "R4") (pin "1") (pinfunction "1_1") (pintype "passive"))
      (node (ref "UC1") (pin "12") (pinfunction "PA2/USART2_TX/ADC12_IN2/TIM2_CH3_12") (pintype "bidirectional"))
    )
    (net (code "48") (name "POT_3") (class "Default")
      (node (ref "C6") (pin "1") (pinfunction "1_1") (pintype "passive"))
      (node (ref "EXPANDER") (pin "3") (pinfunction "2_3") (pintype "passive"))
      (node (ref "IC1") (pin "13") (pinfunction "-IN_13") (pintype "input"))
      (node (ref "J2") (pin "3") (pinfunction "3_3") (pintype "passive"))
      (node (ref "R5") (pin "2") (pinfunction "2_2") (pintype "passive"))
    )
    (net (code "49") (name "POT_3_MCU") (class "Default")
      (node (ref "C6") (pin "2") (pinfunction "2_2") (pintype "passive"))
      (node (ref "IC1") (pin "14") (pinfunction "OUT_14") (pintype "output"))
      (node (ref "R5") (pin "1") (pinfunction "1_1") (pintype "passive"))
      (node (ref "UC1") (pin "11") (pinfunction "PA1/USART2_RTS/ADC12_IN1/TIM2_CH2_11") (pintype "bidirectional"))
    )
    (net (code "50") (name "POT_4") (class "Default")
      (node (ref "C2") (pin "1") (pinfunction "1_1") (pintype "passive"))
      (node (ref "EXPANDER") (pin "4") (pinfunction "9_4") (pintype "passive"))
      (node (ref "IC1") (pin "2") (pinfunction "-IN_2") (pintype "input"))
      (node (ref "J4") (pin "2") (pinfunction "4_2") (pintype "passive"))
      (node (ref "R2") (pin "2") (pinfunction "2_2") (pintype "passive"))
    )
    (net (code "51") (name "POT_4_MCU") (class "Default")
      (node (ref "C2") (pin "2") (pinfunction "2_2") (pintype "passive"))
      (node (ref "IC1") (pin "1") (pinfunction "OUT_1") (pintype "output"))
      (node (ref "R2") (pin "1") (pinfunction "1_1") (pintype "passive"))
      (node (ref "UC1") (pin "10") (pinfunction "PA0_WKUP/USART2_CTS/ADC12_IN0/TIM2_CH1_ETR_10") (pintype "bidirectional"))
    )
    (net (code "52") (name "RESET") (class "Default")
      (node (ref "JTAG") (pin "10") (pinfunction "10_10") (pintype "passive"))
      (node (ref "R7") (pin "1") (pinfunction "1_1") (pintype "passive"))
      (node (ref "RESET") (pin "2") (pinfunction "2_2") (pintype "passive"))
      (node (ref "UC1") (pin "7") (pinfunction "NRST_7") (pintype "input"))
    )
    (net (code "53") (name "RX") (class "Default")
      (node (ref "UC1") (pin "31") (pinfunction "PA10/USART1_RX/TIM1_CH3_31") (pintype "bidirectional"))
    )
    (net (code "54") (name "SW_DUAL") (class "Default")
      (node (ref "J2") (pin "2") (pinfunction "4_2") (pintype "passive"))
      (node (ref "UC1") (pin "3") (pinfunction "PC14-OSC32_IN_3") (pintype "input"))
    )
    (net (code "55") (name "SW_MODE") (class "Default")
      (node (ref "J1") (pin "2") (pinfunction "4_2") (pintype "passive"))
      (node (ref "UC1") (pin "2") (pinfunction "PC13-TAMPER-RTC_2") (pintype "input"))
    )
    (net (code "56") (name "SW_TRIG_1") (class "Default")
      (node (ref "J4") (pin "5") (pinfunction "1_5") (pintype "passive"))
      (node (ref "UC1") (pin "29") (pinfunction "PA8/USART1_CK/TIM1_CH1/MCO_29") (pintype "bidirectional"))
    )
    (net (code "57") (name "SW_TRIG_2") (class "Default")
      (node (ref "J5") (pin "2") (pinfunction "4_2") (pintype "passive"))
      (node (ref "UC1") (pin "40") (pinfunction "PB4/NJTRST_40") (pintype "bidirectional"))
    )
    (net (code "58") (name "TRIG_1") (class "Default")
      (node (ref "J1") (pin "5") (pinfunction "1_5") (pintype "passive"))
      (node (ref "UC1") (pin "22") (pinfunction "PB11/I2C2_SDA/USART3_RX_22") (pintype "input"))
    )
    (net (code "59") (name "TRIG_2") (class "Default")
      (node (ref "J1") (pin "4") (pinfunction "2_4") (pintype "passive"))
      (node (ref "UC1") (pin "33") (pinfunction "PA12/USART1_RTS/CAN_TX/TIM1_ETR/USBDP_33") (pintype "bidirectional"))
    )
    (net (code "60") (name "TX") (class "Default")
      (node (ref "UC1") (pin "30") (pinfunction "PA9/USART1_TX/TIM1_CH2_30") (pintype "input"))
    )
    (net (code "61") (name "VCC") (class "Default")
      (node (ref "C20") (pin "1") (pinfunction "1_1") (pintype "passive"))
      (node (ref "C27") (pin "1") (pinfunction "1_1") (pintype "passive"))
      (node (ref "C28") (pin "+") (pinfunction "+_+") (pintype "passive"))
      (node (ref "D2") (pin "C") (pinfunction "C_C") (pintype "passive"))
      (node (ref "EXPANDER") (pin "7") (pinfunction "4_7") (pintype "passive"))
      (node (ref "EXPANDER") (pin "8") (pinfunction "7_8") (pintype "passive"))
      (node (ref "IC3") (pin "3") (pinfunction "VIN_3") (pintype "input"))
      (node (ref "IC5") (pin "8") (pinfunction "V+_8") (pintype "power_in"))
      (node (ref "IC7") (pin "8") (pinfunction "V+_8") (pintype "power_in"))
    )
    (net (code "62") (name "VEE") (class "Default")
      (node (ref "C19") (pin "2") (pinfunction "2_2") (pintype "passive"))
      (node (ref "C24") (pin "2") (pinfunction "2_2") (pintype "passive"))
      (node (ref "C29") (pin "-") (pinfunction "-_-") (pintype "passive"))
      (node (ref "D1") (pin "A") (pinfunction "A_A") (pintype "passive"))
      (node (ref "EXPANDER") (pin "10") (pinfunction "6_10") (pintype "passive"))
      (node (ref "EXPANDER") (pin "9") (pinfunction "5_9") (pintype "passive"))
      (node (ref "IC5") (pin "4") (pinfunction "V-_4") (pintype "power_in"))
      (node (ref "IC7") (pin "4") (pinfunction "V-_4") (pintype "power_in"))
      (node (ref "R21") (pin "1") (pinfunction "1_1") (pintype "passive"))
    )
    (net (code "63") (name "unconnected-(JTAG-Pad7)") (class "Default")
      (node (ref "JTAG") (pin "7") (pinfunction "7_7") (pintype "passive"))
    )
    (net (code "64") (name "unconnected-(UC1-PA11{slash}USART1_CTS{slash}CAN_RX{slash}TIM1_CH4{slash}USBDM-Pad32)") (class "Default")
      (node (ref "UC1") (pin "32") (pinfunction "PA11/USART1_CTS/CAN_RX/TIM1_CH4/USBDM_32") (pintype "bidirectional"))
    )
    (net (code "65") (name "unconnected-(UC1-PB5{slash}I2C1_SMBA-Pad41)") (class "Default")
      (node (ref "UC1") (pin "41") (pinfunction "PB5/I2C1_SMBA_41") (pintype "input"))
    )
    (net (code "66") (name "unconnected-(UC1-PB6{slash}I2C1_SCL{slash}TIM4_CH1-Pad42)") (class "Default")
      (node (ref "UC1") (pin "42") (pinfunction "PB6/I2C1_SCL/TIM4_CH1_42") (pintype "input"))
    )
    (net (code "67") (name "unconnected-(UC1-PB7{slash}I2C1_SDA{slash}TIM4_CH2-Pad43)") (class "Default")
      (node (ref "UC1") (pin "43") (pinfunction "PB7/I2C1_SDA/TIM4_CH2_43") (pintype "bidirectional"))
    )
    (net (code "68") (name "unconnected-(UC1-PB8{slash}TIM4_CH3-Pad45)") (class "Default")
      (node (ref "UC1") (pin "45") (pinfunction "PB8/TIM4_CH3_45") (pintype "bidirectional"))
    )
    (net (code "69") (name "unconnected-(UC1-PB14{slash}SPI2_MISO{slash}USART3_RTS{slash}TIM1_CH2N-Pad27)") (class "Default")
      (node (ref "UC1") (pin "27") (pinfunction "PB14/SPI2_MISO/USART3_RTS/TIM1_CH2N_27") (pintype "input"))
    )
    (net (code "70") (name "unconnected-(UC1-PC15-OSC32_OUT-Pad4)") (class "Default")
      (node (ref "UC1") (pin "4") (pinfunction "PC15-OSC32_OUT_4") (pintype "input"))
    )
  )
)
